# LazeRX-9c.net
KiCad netlist of a schematic drawn in Altium Designer
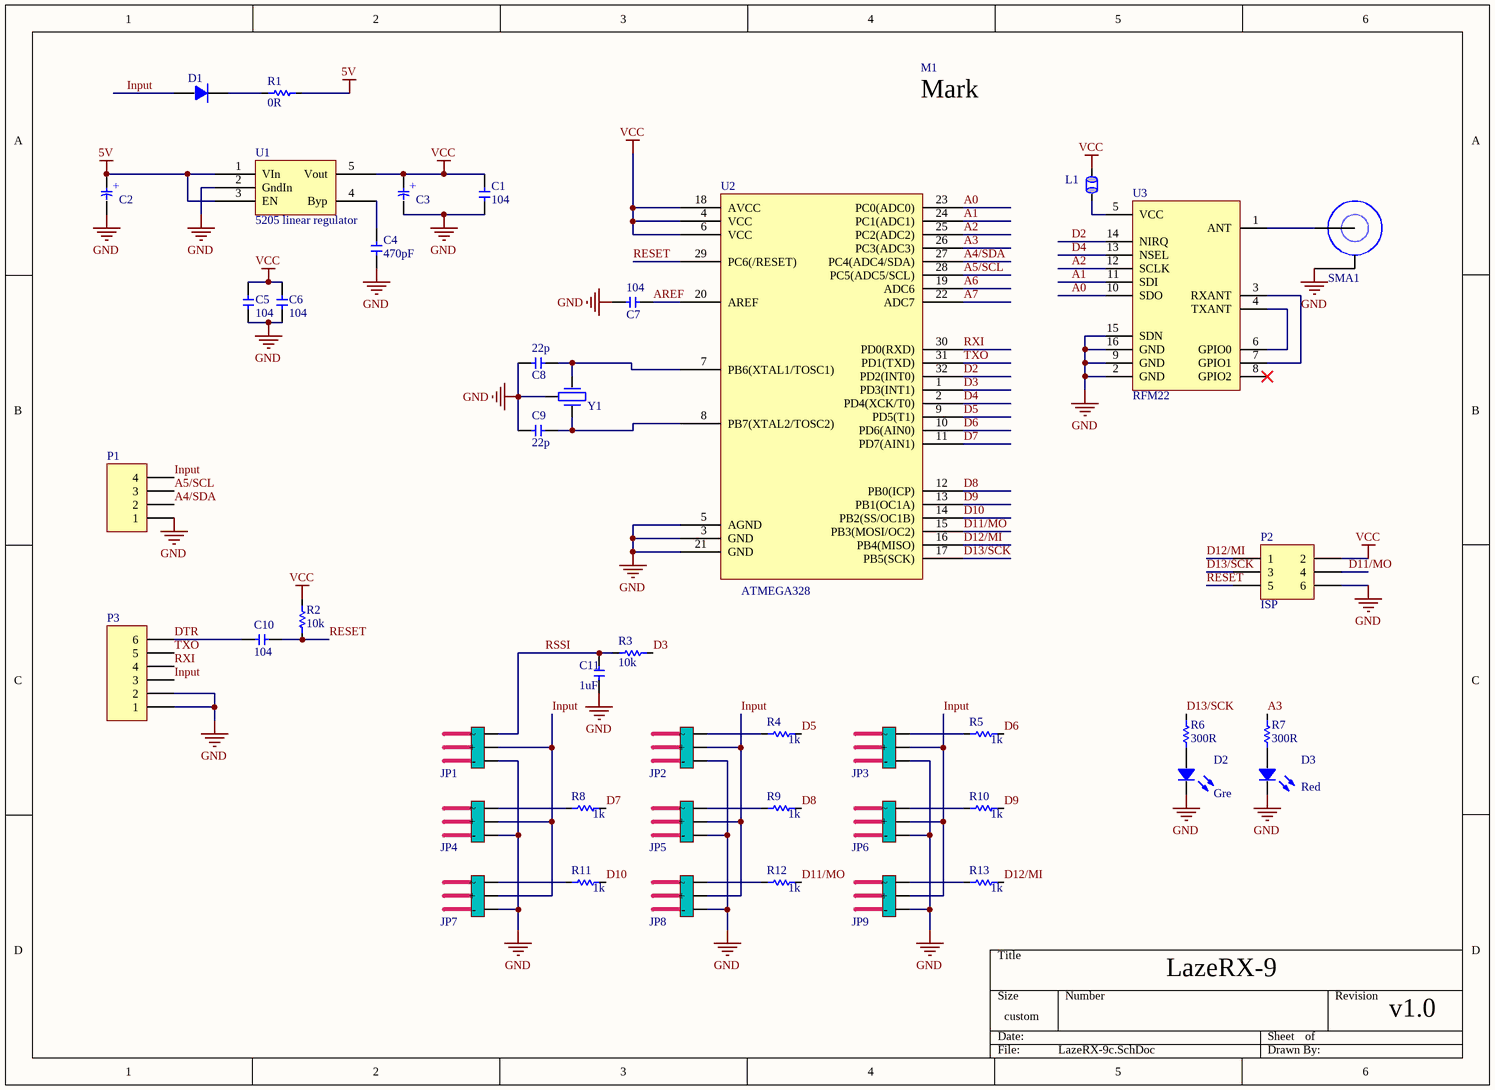
[diagram p0: LazeRX-9c.SchDoc]

(export (version "E")
  (design (tool "Eeschema 10.0.6"))
  (components
    (comp (ref "C1")
      (value "104")
      (footprint "0603 CAP")
      (description "Capacitor")
      (fields (field (name "PUBLISHER") "Altium Limited"))
      (libsource (lib "Drone") (part "CAP"))
    )
    (comp (ref "C2")
      (value "4.7uF/6.3V")
      (footprint "1206")
      (description "Capacitor")
      (libsource (lib "Drone") (part "Cap Pol"))
    )
    (comp (ref "C3")
      (value "4.7uF/6.3V")
      (footprint "1206 CAP")
      (description "Capacitor")
      (libsource (lib "Drone") (part "Cap Pol"))
    )
    (comp (ref "C4")
      (value "470pF")
      (footprint "0603 CAP")
      (description "Capacitor")
      (fields (field (name "PUBLISHER") "Altium Limited"))
      (libsource (lib "Drone") (part "CAP"))
    )
    (comp (ref "C5")
      (value "104")
      (footprint "0603 CAP")
      (description "Capacitor")
      (fields (field (name "PUBLISHER") "Altium Limited"))
      (libsource (lib "Drone") (part "CAP"))
    )
    (comp (ref "C6")
      (value "104")
      (footprint "0603 CAP")
      (description "Capacitor")
      (fields (field (name "PUBLISHER") "Altium Limited"))
      (libsource (lib "Drone") (part "CAP"))
    )
    (comp (ref "C7")
      (value "104")
      (footprint "0603 CAP")
      (description "Capacitor")
      (fields (field (name "PUBLISHER") "Altium Limited"))
      (libsource (lib "Drone") (part "CAP"))
    )
    (comp (ref "C8")
      (value "22p")
      (footprint "0603 CAP")
      (description "Capacitor")
      (fields (field (name "PUBLISHER") "Altium Limited"))
      (libsource (lib "Drone") (part "CAP"))
    )
    (comp (ref "C9")
      (value "22p")
      (footprint "0603 CAP")
      (description "Capacitor")
      (fields (field (name "PUBLISHER") "Altium Limited"))
      (libsource (lib "Drone") (part "CAP"))
    )
    (comp (ref "C10")
      (value "104")
      (footprint "0603 CAP")
      (description "Capacitor")
      (fields (field (name "PUBLISHER") "Altium Limited"))
      (libsource (lib "Drone") (part "CAP"))
    )
    (comp (ref "C11")
      (value "1uF")
      (footprint "0603 CAP")
      (description "Capacitor")
      (fields (field (name "PUBLISHER") "Altium Limited"))
      (libsource (lib "Drone") (part "CAP"))
    )
    (comp (ref "D1") (value "Diode") (footprint "DIODE-SOD123") (libsource (lib "Drone") (part "Diode")))
    (comp (ref "D2")
      (value "Gre")
      (footprint "0805 LED")
      (description "Typical RED, GREEN, YELLOW, AMBER GaAs LED")
      (fields (field (name "PUBLISHER") "Altium Limited"))
      (libsource (lib "Drone") (part "LED"))
    )
    (comp (ref "D3")
      (value "Red")
      (footprint "0805 LED")
      (description "Typical RED, GREEN, YELLOW, AMBER GaAs LED")
      (fields (field (name "PUBLISHER") "Altium Limited"))
      (libsource (lib "Drone") (part "LED"))
    )
    (comp (ref "JP1")
      (value "Servo out 1")
      (footprint "JP - compact")
      (description "Header, 3-Pin, 0.1\"")
      (fields (field (name "MANUFACTURER") "Generic Components"))
      (libsource (lib "Drone") (part "Hdr 3 Pin 0.1"))
    )
    (comp (ref "JP2")
      (value "Servo out 1")
      (footprint "JP - compact")
      (description "Header, 3-Pin, 0.1\"")
      (fields (field (name "MANUFACTURER") "Generic Components"))
      (libsource (lib "Drone") (part "Hdr 3 Pin 0.1"))
    )
    (comp (ref "JP3")
      (value "Servo out 1")
      (footprint "JP - compact")
      (description "Header, 3-Pin, 0.1\"")
      (fields (field (name "MANUFACTURER") "Generic Components"))
      (libsource (lib "Drone") (part "Hdr 3 Pin 0.1"))
    )
    (comp (ref "JP4")
      (value "Servo out 1")
      (footprint "JP - compact")
      (description "Header, 3-Pin, 0.1\"")
      (fields (field (name "MANUFACTURER") "Generic Components"))
      (libsource (lib "Drone") (part "Hdr 3 Pin 0.1"))
    )
    (comp (ref "JP5")
      (value "Servo out 1")
      (footprint "JP - compact")
      (description "Header, 3-Pin, 0.1\"")
      (fields (field (name "MANUFACTURER") "Generic Components"))
      (libsource (lib "Drone") (part "Hdr 3 Pin 0.1"))
    )
    (comp (ref "JP6")
      (value "Servo out 1")
      (footprint "JP - compact")
      (description "Header, 3-Pin, 0.1\"")
      (fields (field (name "MANUFACTURER") "Generic Components"))
      (libsource (lib "Drone") (part "Hdr 3 Pin 0.1"))
    )
    (comp (ref "JP7")
      (value "Servo out 1")
      (footprint "JP - compact")
      (description "Header, 3-Pin, 0.1\"")
      (fields (field (name "MANUFACTURER") "Generic Components"))
      (libsource (lib "Drone") (part "Hdr 3 Pin 0.1"))
    )
    (comp (ref "JP8")
      (value "Servo out 1")
      (footprint "JP - compact")
      (description "Header, 3-Pin, 0.1\"")
      (fields (field (name "MANUFACTURER") "Generic Components"))
      (libsource (lib "Drone") (part "Hdr 3 Pin 0.1"))
    )
    (comp (ref "JP9")
      (value "Servo out 1")
      (footprint "JP - compact")
      (description "Header, 3-Pin, 0.1\"")
      (fields (field (name "MANUFACTURER") "Generic Components"))
      (libsource (lib "Drone") (part "Hdr 3 Pin 0.1"))
    )
    (comp (ref "L1")
      (value "FB 300mA")
      (footprint "0603 IND")
      (description "Ferrite Bead 300mA")
      (fields (field (name "MANUFACTURER") "Generic Components"))
      (libsource (lib "Drone") (part "FerriteBead_300mA"))
    )
    (comp (ref "M1") (value "Mark") (footprint "MarkPoint") (libsource (lib "Drone") (part "Mark")))
    (comp (ref "P1")
      (value "Header 4")
      (footprint "HDR1X4")
      (description "Header, 4-Pin")
      (fields (field (name "PUBLISHER") "Altium Limited"))
      (libsource (lib "Miscellaneous Connectors") (part "Header 4"))
    )
    (comp (ref "P2")
      (value "ISP")
      (footprint "HDR2X3")
      (description "Header, 3-Pin, Dual row")
      (fields (field (name "PUBLISHER") "Altium Limited"))
      (libsource (lib "Miscellaneous Connectors") (part "Header 3X2"))
    )
    (comp (ref "P3")
      (value "Header 6")
      (footprint "HDR1X6")
      (description "Header, 6-Pin")
      (fields (field (name "PUBLISHER") "Altium Limited"))
      (libsource (lib "Miscellaneous Connectors") (part "Header 6"))
    )
    (comp (ref "R1")
      (value "0R")
      (footprint "0603 RES")
      (description "Resistor")
      (fields (field (name "PUBLISHER") "Altium Limited"))
      (libsource (lib "Drone") (part "Res"))
    )
    (comp (ref "R2")
      (value "10k")
      (footprint "0603 RES")
      (description "Resistor")
      (fields (field (name "PUBLISHER") "Altium Limited"))
      (libsource (lib "Drone") (part "Res"))
    )
    (comp (ref "R3")
      (value "10k")
      (footprint "0603 RES")
      (description "Resistor")
      (fields (field (name "PUBLISHER") "Altium Limited"))
      (libsource (lib "Drone") (part "Res"))
    )
    (comp (ref "R4")
      (value "1k")
      (footprint "0603 RES")
      (description "Resistor")
      (fields (field (name "PUBLISHER") "Altium Limited"))
      (libsource (lib "Drone") (part "Res"))
    )
    (comp (ref "R5")
      (value "1k")
      (footprint "0603 RES")
      (description "Resistor")
      (fields (field (name "PUBLISHER") "Altium Limited"))
      (libsource (lib "Drone") (part "Res"))
    )
    (comp (ref "R6")
      (value "300R")
      (footprint "0603 RES")
      (description "Resistor")
      (fields (field (name "PUBLISHER") "Altium Limited"))
      (libsource (lib "Drone") (part "Res"))
    )
    (comp (ref "R7")
      (value "300R")
      (footprint "0603 RES")
      (description "Resistor")
      (fields (field (name "PUBLISHER") "Altium Limited"))
      (libsource (lib "Drone") (part "Res"))
    )
    (comp (ref "R8")
      (value "1k")
      (footprint "0603 RES")
      (description "Resistor")
      (fields (field (name "PUBLISHER") "Altium Limited"))
      (libsource (lib "Drone") (part "Res"))
    )
    (comp (ref "R9")
      (value "1k")
      (footprint "0603 RES")
      (description "Resistor")
      (fields (field (name "PUBLISHER") "Altium Limited"))
      (libsource (lib "Drone") (part "Res"))
    )
    (comp (ref "R10")
      (value "1k")
      (footprint "0603 RES")
      (description "Resistor")
      (fields (field (name "PUBLISHER") "Altium Limited"))
      (libsource (lib "Drone") (part "Res"))
    )
    (comp (ref "R11")
      (value "1k")
      (footprint "0603 RES")
      (description "Resistor")
      (fields (field (name "PUBLISHER") "Altium Limited"))
      (libsource (lib "Drone") (part "Res"))
    )
    (comp (ref "R12")
      (value "1k")
      (footprint "0603 RES")
      (description "Resistor")
      (fields (field (name "PUBLISHER") "Altium Limited"))
      (libsource (lib "Drone") (part "Res"))
    )
    (comp (ref "R13")
      (value "1k")
      (footprint "0603 RES")
      (description "Resistor")
      (fields (field (name "PUBLISHER") "Altium Limited"))
      (libsource (lib "Drone") (part "Res"))
    )
    (comp (ref "SMA1") (value "SMA Base") (footprint "ANT SMA") (libsource (lib "Drone") (part "SMA Base")))
    (comp (ref "U1")
      (value "5205 linear regulator")
      (footprint "5205")
      (libsource (lib "Drone") (part "5205 linear regulator"))
    )
    (comp (ref "U2")
      (value "ATmega328")
      (footprint "ATMEGA328FIX")
      (libsource (lib "Drone") (part "ATmega328"))
    )
    (comp (ref "U3") (value "RFM22") (footprint "RFM22SMD") (libsource (lib "Drone") (part "RFM22")))
    (comp (ref "Y1")
      (value "Crystal3Foot")
      (footprint "Crystal3Foot")
      (libsource (lib "Drone") (part "Crystal3Foot"))
    )
  )
  (nets
    (net (code "1") (name "/A0") (class "Default")
      (node (ref "U2") (pin "23") (pinfunction "PC0(ADC0)_23") (pintype "passive"))
      (node (ref "U3") (pin "10") (pinfunction "SDO_10") (pintype "passive"))
    )
    (net (code "2") (name "/A1") (class "Default")
      (node (ref "U2") (pin "24") (pinfunction "PC1(ADC1)_24") (pintype "passive"))
      (node (ref "U3") (pin "11") (pinfunction "SDI_11") (pintype "passive"))
    )
    (net (code "3") (name "/A2") (class "Default")
      (node (ref "U2") (pin "25") (pinfunction "PC2(ADC2)_25") (pintype "passive"))
      (node (ref "U3") (pin "12") (pinfunction "SCLK_12") (pintype "passive"))
    )
    (net (code "4") (name "/A3") (class "Default")
      (node (ref "R7") (pin "2") (pinfunction "2_2") (pintype "passive"))
      (node (ref "U2") (pin "26") (pinfunction "PC3(ADC3)_26") (pintype "passive"))
    )
    (net (code "5") (name "/A4{slash}SDA") (class "Default")
      (node (ref "P1") (pin "2") (pinfunction "2_2") (pintype "passive"))
      (node (ref "U2") (pin "27") (pinfunction "PC4(ADC4/SDA)_27") (pintype "passive"))
    )
    (net (code "6") (name "/A5{slash}SCL") (class "Default")
      (node (ref "P1") (pin "3") (pinfunction "3_3") (pintype "passive"))
      (node (ref "U2") (pin "28") (pinfunction "PC5(ADC5/SCL)_28") (pintype "passive"))
    )
    (net (code "7") (name "/A6") (class "Default")
      (node (ref "U2") (pin "19") (pinfunction "ADC6_19") (pintype "passive"))
    )
    (net (code "8") (name "/A7") (class "Default")
      (node (ref "U2") (pin "22") (pinfunction "ADC7_22") (pintype "passive"))
    )
    (net (code "9") (name "/AREF") (class "Default")
      (node (ref "C7") (pin "2") (pinfunction "2_2") (pintype "passive"))
      (node (ref "U2") (pin "20") (pinfunction "AREF_20") (pintype "passive"))
    )
    (net (code "10") (name "/D2") (class "Default")
      (node (ref "U2") (pin "32") (pinfunction "PD2(INT0)_32") (pintype "passive"))
      (node (ref "U3") (pin "14") (pinfunction "NIRQ_14") (pintype "passive"))
    )
    (net (code "11") (name "/D3") (class "Default")
      (node (ref "R3") (pin "1") (pinfunction "1_1") (pintype "passive"))
      (node (ref "U2") (pin "1") (pinfunction "PD3(INT1)_1") (pintype "passive"))
    )
    (net (code "12") (name "/D4") (class "Default")
      (node (ref "U2") (pin "2") (pinfunction "PD4(XCK/T0)_2") (pintype "passive"))
      (node (ref "U3") (pin "13") (pinfunction "NSEL_13") (pintype "passive"))
    )
    (net (code "13") (name "/D5") (class "Default")
      (node (ref "R4") (pin "1") (pinfunction "1_1") (pintype "passive"))
      (node (ref "U2") (pin "9") (pinfunction "PD5(T1)_9") (pintype "passive"))
    )
    (net (code "14") (name "/D6") (class "Default")
      (node (ref "R5") (pin "1") (pinfunction "1_1") (pintype "passive"))
      (node (ref "U2") (pin "10") (pinfunction "PD6(AIN0)_10") (pintype "passive"))
    )
    (net (code "15") (name "/D7") (class "Default")
      (node (ref "R8") (pin "1") (pinfunction "1_1") (pintype "passive"))
      (node (ref "U2") (pin "11") (pinfunction "PD7(AIN1)_11") (pintype "passive"))
    )
    (net (code "16") (name "/D8") (class "Default")
      (node (ref "R9") (pin "1") (pinfunction "1_1") (pintype "passive"))
      (node (ref "U2") (pin "12") (pinfunction "PB0(ICP)_12") (pintype "passive"))
    )
    (net (code "17") (name "/D9") (class "Default")
      (node (ref "R10") (pin "1") (pinfunction "1_1") (pintype "passive"))
      (node (ref "U2") (pin "13") (pinfunction "PB1(OC1A)_13") (pintype "passive"))
    )
    (net (code "18") (name "/D10") (class "Default")
      (node (ref "R11") (pin "1") (pinfunction "1_1") (pintype "passive"))
      (node (ref "U2") (pin "14") (pinfunction "PB2(SS/OC1B)_14") (pintype "passive"))
    )
    (net (code "19") (name "/D11{slash}MO") (class "Default")
      (node (ref "P2") (pin "4") (pinfunction "4_4") (pintype "passive"))
      (node (ref "R12") (pin "1") (pinfunction "1_1") (pintype "passive"))
      (node (ref "U2") (pin "15") (pinfunction "PB3(MOSI/OC2)_15") (pintype "passive"))
    )
    (net (code "20") (name "/D12{slash}MI") (class "Default")
      (node (ref "P2") (pin "1") (pinfunction "1_1") (pintype "passive"))
      (node (ref "R13") (pin "1") (pinfunction "1_1") (pintype "passive"))
      (node (ref "U2") (pin "16") (pinfunction "PB4(MISO)_16") (pintype "passive"))
    )
    (net (code "21") (name "/D13{slash}SCK") (class "Default")
      (node (ref "P2") (pin "3") (pinfunction "3_3") (pintype "passive"))
      (node (ref "R6") (pin "2") (pinfunction "2_2") (pintype "passive"))
      (node (ref "U2") (pin "17") (pinfunction "PB5(SCK)_17") (pintype "passive"))
    )
    (net (code "22") (name "/DTR") (class "Default")
      (node (ref "C10") (pin "2") (pinfunction "2_2") (pintype "passive"))
      (node (ref "P3") (pin "6") (pinfunction "6_6") (pintype "passive"))
    )
    (net (code "23") (name "/Input") (class "Default")
      (node (ref "D1") (pin "1") (pinfunction "A_1") (pintype "passive"))
      (node (ref "JP1") (pin "2") (pinfunction "+_2") (pintype "passive"))
      (node (ref "JP2") (pin "2") (pinfunction "+_2") (pintype "passive"))
      (node (ref "JP3") (pin "2") (pinfunction "+_2") (pintype "passive"))
      (node (ref "JP4") (pin "2") (pinfunction "+_2") (pintype "passive"))
      (node (ref "JP5") (pin "2") (pinfunction "+_2") (pintype "passive"))
      (node (ref "JP6") (pin "2") (pinfunction "+_2") (pintype "passive"))
      (node (ref "JP7") (pin "2") (pinfunction "+_2") (pintype "passive"))
      (node (ref "JP8") (pin "2") (pinfunction "+_2") (pintype "passive"))
      (node (ref "JP9") (pin "2") (pinfunction "+_2") (pintype "passive"))
      (node (ref "P1") (pin "4") (pinfunction "4_4") (pintype "passive"))
      (node (ref "P3") (pin "3") (pinfunction "3_3") (pintype "passive"))
    )
    (net (code "24") (name "/RESET") (class "Default")
      (node (ref "C10") (pin "1") (pinfunction "1_1") (pintype "passive"))
      (node (ref "P2") (pin "5") (pinfunction "5_5") (pintype "passive"))
      (node (ref "R2") (pin "2") (pinfunction "2_2") (pintype "passive"))
      (node (ref "U2") (pin "29") (pinfunction "PC6(/RESET)_29") (pintype "passive"))
    )
    (net (code "25") (name "/RSSI") (class "Default")
      (node (ref "C11") (pin "2") (pinfunction "2_2") (pintype "passive"))
      (node (ref "JP1") (pin "1") (pinfunction "~_1") (pintype "passive"))
      (node (ref "R3") (pin "2") (pinfunction "2_2") (pintype "passive"))
    )
    (net (code "26") (name "/RXI") (class "Default")
      (node (ref "P3") (pin "4") (pinfunction "4_4") (pintype "passive"))
      (node (ref "U2") (pin "30") (pinfunction "PD0(RXD)_30") (pintype "passive"))
    )
    (net (code "27") (name "/TXO") (class "Default")
      (node (ref "P3") (pin "5") (pinfunction "5_5") (pintype "passive"))
      (node (ref "U2") (pin "31") (pinfunction "PD1(TXD)_31") (pintype "passive"))
    )
    (net (code "28") (name "5V") (class "Default")
      (node (ref "C2") (pin "1") (pinfunction "A_1") (pintype "passive"))
      (node (ref "R1") (pin "1") (pinfunction "1_1") (pintype "passive"))
      (node (ref "U1") (pin "1") (pinfunction "VIn_1") (pintype "passive"))
      (node (ref "U1") (pin "3") (pinfunction "EN_3") (pintype "passive"))
    )
    (net (code "29") (name "GND") (class "Default")
      (node (ref "C1") (pin "1") (pinfunction "1_1") (pintype "passive"))
      (node (ref "C11") (pin "1") (pinfunction "1_1") (pintype "passive"))
      (node (ref "C2") (pin "2") (pinfunction "B_2") (pintype "passive"))
      (node (ref "C3") (pin "2") (pinfunction "B_2") (pintype "passive"))
      (node (ref "C4") (pin "1") (pinfunction "1_1") (pintype "passive"))
      (node (ref "C5") (pin "1") (pinfunction "1_1") (pintype "passive"))
      (node (ref "C6") (pin "1") (pinfunction "1_1") (pintype "passive"))
      (node (ref "C7") (pin "1") (pinfunction "1_1") (pintype "passive"))
      (node (ref "C8") (pin "1") (pinfunction "1_1") (pintype "passive"))
      (node (ref "C9") (pin "1") (pinfunction "1_1") (pintype "passive"))
      (node (ref "D2") (pin "2") (pinfunction "K_2") (pintype "passive"))
      (node (ref "D3") (pin "2") (pinfunction "K_2") (pintype "passive"))
      (node (ref "JP1") (pin "3") (pinfunction "-_3") (pintype "passive"))
      (node (ref "JP2") (pin "3") (pinfunction "-_3") (pintype "passive"))
      (node (ref "JP3") (pin "3") (pinfunction "-_3") (pintype "passive"))
      (node (ref "JP4") (pin "3") (pinfunction "-_3") (pintype "passive"))
      (node (ref "JP5") (pin "3") (pinfunction "-_3") (pintype "passive"))
      (node (ref "JP6") (pin "3") (pinfunction "-_3") (pintype "passive"))
      (node (ref "JP7") (pin "3") (pinfunction "-_3") (pintype "passive"))
      (node (ref "JP8") (pin "3") (pinfunction "-_3") (pintype "passive"))
      (node (ref "JP9") (pin "3") (pinfunction "-_3") (pintype "passive"))
      (node (ref "P1") (pin "1") (pinfunction "1_1") (pintype "passive"))
      (node (ref "P2") (pin "6") (pinfunction "6_6") (pintype "passive"))
      (node (ref "P3") (pin "1") (pinfunction "1_1") (pintype "passive"))
      (node (ref "P3") (pin "2") (pinfunction "2_2") (pintype "passive"))
      (node (ref "SMA1") (pin "2") (pinfunction "Gnd_2") (pintype "passive"))
      (node (ref "U1") (pin "2") (pinfunction "GndIn_2") (pintype "passive"))
      (node (ref "U2") (pin "21") (pinfunction "GND_21") (pintype "passive"))
      (node (ref "U2") (pin "3") (pinfunction "GND_3") (pintype "passive"))
      (node (ref "U2") (pin "5") (pinfunction "AGND_5") (pintype "passive"))
      (node (ref "U3") (pin "15") (pinfunction "SDN_15") (pintype "passive"))
      (node (ref "U3") (pin "16") (pinfunction "GND_16") (pintype "passive"))
      (node (ref "U3") (pin "2") (pinfunction "GND_2") (pintype "passive"))
      (node (ref "U3") (pin "9") (pinfunction "GND_9") (pintype "passive"))
      (node (ref "Y1") (pin "2") (pinfunction "2_2") (pintype "passive"))
    )
    (net (code "30") (name "Net-(D1-B)") (class "Default")
      (node (ref "D1") (pin "2") (pinfunction "B_2") (pintype "passive"))
      (node (ref "R1") (pin "2") (pinfunction "2_2") (pintype "passive"))
    )
    (net (code "31") (name "Net-(D2-A)") (class "Default")
      (node (ref "D2") (pin "1") (pinfunction "A_1") (pintype "passive"))
      (node (ref "R6") (pin "1") (pinfunction "1_1") (pintype "passive"))
    )
    (net (code "32") (name "Net-(D3-A)") (class "Default")
      (node (ref "D3") (pin "1") (pinfunction "A_1") (pintype "passive"))
      (node (ref "R7") (pin "1") (pinfunction "1_1") (pintype "passive"))
    )
    (net (code "33") (name "Net-(JP2-~)") (class "Default")
      (node (ref "JP2") (pin "1") (pinfunction "~_1") (pintype "passive"))
      (node (ref "R4") (pin "2") (pinfunction "2_2") (pintype "passive"))
    )
    (net (code "34") (name "Net-(JP3-~)") (class "Default")
      (node (ref "JP3") (pin "1") (pinfunction "~_1") (pintype "passive"))
      (node (ref "R5") (pin "2") (pinfunction "2_2") (pintype "passive"))
    )
    (net (code "35") (name "Net-(JP4-~)") (class "Default")
      (node (ref "JP4") (pin "1") (pinfunction "~_1") (pintype "passive"))
      (node (ref "R8") (pin "2") (pinfunction "2_2") (pintype "passive"))
    )
    (net (code "36") (name "Net-(JP5-~)") (class "Default")
      (node (ref "JP5") (pin "1") (pinfunction "~_1") (pintype "passive"))
      (node (ref "R9") (pin "2") (pinfunction "2_2") (pintype "passive"))
    )
    (net (code "37") (name "Net-(JP6-~)") (class "Default")
      (node (ref "JP6") (pin "1") (pinfunction "~_1") (pintype "passive"))
      (node (ref "R10") (pin "2") (pinfunction "2_2") (pintype "passive"))
    )
    (net (code "38") (name "Net-(JP7-~)") (class "Default")
      (node (ref "JP7") (pin "1") (pinfunction "~_1") (pintype "passive"))
      (node (ref "R11") (pin "2") (pinfunction "2_2") (pintype "passive"))
    )
    (net (code "39") (name "Net-(JP8-~)") (class "Default")
      (node (ref "JP8") (pin "1") (pinfunction "~_1") (pintype "passive"))
      (node (ref "R12") (pin "2") (pinfunction "2_2") (pintype "passive"))
    )
    (net (code "40") (name "Net-(JP9-~)") (class "Default")
      (node (ref "JP9") (pin "1") (pinfunction "~_1") (pintype "passive"))
      (node (ref "R13") (pin "2") (pinfunction "2_2") (pintype "passive"))
    )
    (net (code "41") (name "Net-(SMA1-Ant)") (class "Default")
      (node (ref "SMA1") (pin "1") (pinfunction "Ant_1") (pintype "passive"))
      (node (ref "U3") (pin "1") (pinfunction "ANT_1") (pintype "passive"))
    )
    (net (code "42") (name "Net-(U1-Byp)") (class "Default")
      (node (ref "C4") (pin "2") (pinfunction "2_2") (pintype "passive"))
      (node (ref "U1") (pin "4") (pinfunction "Byp_4") (pintype "passive"))
    )
    (net (code "43") (name "Net-(U2-PB6(XTAL1{slash}TOSC1))") (class "Default")
      (node (ref "C8") (pin "2") (pinfunction "2_2") (pintype "passive"))
      (node (ref "U2") (pin "7") (pinfunction "PB6(XTAL1/TOSC1)_7") (pintype "passive"))
      (node (ref "Y1") (pin "1") (pinfunction "0_1") (pintype "passive"))
    )
    (net (code "44") (name "Net-(U2-PB7(XTAL2{slash}TOSC2))") (class "Default")
      (node (ref "C9") (pin "2") (pinfunction "2_2") (pintype "passive"))
      (node (ref "U2") (pin "8") (pinfunction "PB7(XTAL2/TOSC2)_8") (pintype "passive"))
      (node (ref "Y1") (pin "3") (pinfunction "1_3") (pintype "passive"))
    )
    (net (code "45") (name "Net-(U3-GPIO0)") (class "Default")
      (node (ref "U3") (pin "4") (pinfunction "TXANT_4") (pintype "passive"))
      (node (ref "U3") (pin "6") (pinfunction "GPIO0_6") (pintype "passive"))
    )
    (net (code "46") (name "Net-(U3-GPIO1)") (class "Default")
      (node (ref "U3") (pin "3") (pinfunction "RXANT_3") (pintype "passive"))
      (node (ref "U3") (pin "7") (pinfunction "GPIO1_7") (pintype "passive"))
    )
    (net (code "47") (name "Net-(U3-VCC)") (class "Default")
      (node (ref "L1") (pin "1") (pinfunction "1_1") (pintype "passive"))
      (node (ref "U3") (pin "5") (pinfunction "VCC_5") (pintype "passive"))
    )
    (net (code "48") (name "VCC") (class "Default")
      (node (ref "C1") (pin "2") (pinfunction "2_2") (pintype "passive"))
      (node (ref "C3") (pin "1") (pinfunction "A_1") (pintype "passive"))
      (node (ref "C5") (pin "2") (pinfunction "2_2") (pintype "passive"))
      (node (ref "C6") (pin "2") (pinfunction "2_2") (pintype "passive"))
      (node (ref "L1") (pin "2") (pinfunction "2_2") (pintype "passive"))
      (node (ref "P2") (pin "2") (pinfunction "2_2") (pintype "passive"))
      (node (ref "R2") (pin "1") (pinfunction "1_1") (pintype "passive"))
      (node (ref "U1") (pin "5") (pinfunction "Vout_5") (pintype "passive"))
      (node (ref "U2") (pin "18") (pinfunction "AVCC_18") (pintype "passive"))
      (node (ref "U2") (pin "4") (pinfunction "VCC_4") (pintype "passive"))
      (node (ref "U2") (pin "6") (pinfunction "VCC_6") (pintype "passive"))
    )
    (net (code "49") (name "unconnected-(U3-GPIO2-Pad8)") (class "Default")
      (node (ref "U3") (pin "8") (pinfunction "GPIO2_8") (pintype "passive+no_connect"))
    )
  )
)
